# dummyvideo.net
KiCad netlist of a schematic drawn in EAGLE
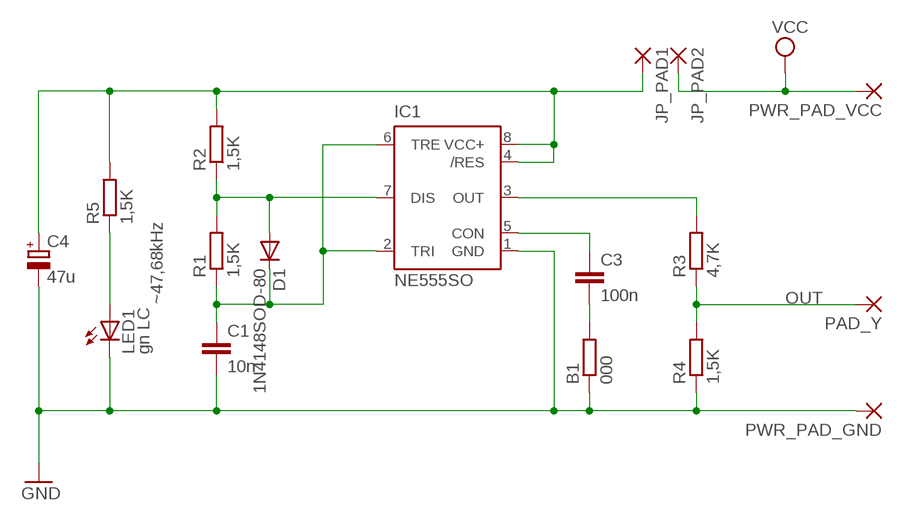
[diagram p0: schematic, sheet 1]

(export (version "E")
  (design (tool "Eeschema 10.0.6"))
  (components
    (comp (ref "B1")
      (value "000")
      (footprint "eagle-import:R1206")
      (libsource (lib "eagle-import") (part "R-EU_R1206"))
    )
    (comp (ref "C1")
      (value "10n")
      (footprint "eagle-import:C0805")
      (libsource (lib "eagle-import") (part "C-EUC0805"))
    )
    (comp (ref "C3")
      (value "100n")
      (footprint "eagle-import:C0805")
      (libsource (lib "eagle-import") (part "C-EUC0805"))
    )
    (comp (ref "C4")
      (value "47u")
      (footprint "eagle-import:153CLV-0505")
      (libsource (lib "eagle-import") (part "CPOL-EU153CLV-0505"))
    )
    (comp (ref "D1")
      (value "1N4148SOD-80")
      (footprint "eagle-import:SOD80C")
      (libsource (lib "eagle-import") (part "1N4148SOD-80"))
    )
    (comp (ref "IC1")
      (value "NE555SO")
      (footprint "eagle-import:SO08")
      (fields (field (name "MPN") "NE555D"))
      (libsource (lib "eagle-import") (part "NE555SO"))
    )
    (comp (ref "JP_PAD1")
      (value "SMD2")
      (footprint "eagle-import:SMD1,27-2,54")
      (libsource (lib "eagle-import") (part "SMD2"))
    )
    (comp (ref "JP_PAD2")
      (value "SMD2")
      (footprint "eagle-import:SMD1,27-2,54")
      (libsource (lib "eagle-import") (part "SMD2"))
    )
    (comp (ref "LED1")
      (value "gn LC")
      (footprint "eagle-import:CHIP-LED0603")
      (libsource (lib "eagle-import") (part "LEDCHIP-LED0603"))
    )
    (comp (ref "PAD_Y")
      (value "SMD2")
      (footprint "eagle-import:SMD1,27-2,54")
      (libsource (lib "eagle-import") (part "SMD2"))
    )
    (comp (ref "PWR_PAD_GND")
      (value "SMD2")
      (footprint "eagle-import:SMD1,27-2,54")
      (libsource (lib "eagle-import") (part "SMD2"))
    )
    (comp (ref "PWR_PAD_VCC")
      (value "SMD2")
      (footprint "eagle-import:SMD1,27-2,54")
      (libsource (lib "eagle-import") (part "SMD2"))
    )
    (comp (ref "R1")
      (value "1,5K")
      (footprint "eagle-import:R0805")
      (libsource (lib "eagle-import") (part "R-EU_R0805"))
    )
    (comp (ref "R2")
      (value "1,5K")
      (footprint "eagle-import:M0805")
      (libsource (lib "eagle-import") (part "R-EU_M0805"))
    )
    (comp (ref "R3")
      (value "4,7K")
      (footprint "eagle-import:R0805")
      (libsource (lib "eagle-import") (part "R-EU_R0805"))
    )
    (comp (ref "R4")
      (value "1,5K")
      (footprint "eagle-import:R0805")
      (libsource (lib "eagle-import") (part "R-EU_R0805"))
    )
    (comp (ref "R5")
      (value "1,5K")
      (footprint "eagle-import:R0805")
      (libsource (lib "eagle-import") (part "R-EU_R0805"))
    )
  )
  (nets
    (net (code "1") (name "/OUT") (class "Default")
      (node (ref "PAD_Y") (pin "1") (pinfunction "P_1") (pintype "passive"))
      (node (ref "R3") (pin "1") (pinfunction "1_1") (pintype "passive"))
      (node (ref "R4") (pin "2") (pinfunction "2_2") (pintype "passive"))
    )
    (net (code "2") (name "GND") (class "Default")
      (node (ref "B1") (pin "1") (pinfunction "1_1") (pintype "passive"))
      (node (ref "B1") (pin "2") (pinfunction "2_2") (pintype "passive"))
      (node (ref "C1") (pin "2") (pinfunction "2_2") (pintype "passive"))
      (node (ref "C3") (pin "2") (pinfunction "2_2") (pintype "passive"))
      (node (ref "C4") (pin "-") (pinfunction "-_-") (pintype "passive"))
      (node (ref "IC1") (pin "1") (pinfunction "GND_1") (pintype "power_in"))
      (node (ref "LED1") (pin "C") (pinfunction "C_C") (pintype "passive"))
      (node (ref "PWR_PAD_GND") (pin "1") (pinfunction "P_1") (pintype "passive"))
      (node (ref "R4") (pin "1") (pinfunction "1_1") (pintype "passive"))
    )
    (net (code "3") (name "Net-(IC1-CON)") (class "Default")
      (node (ref "C3") (pin "1") (pinfunction "1_1") (pintype "passive"))
      (node (ref "IC1") (pin "5") (pinfunction "CON_5") (pintype "input"))
    )
    (net (code "4") (name "Net-(IC1-DIS)") (class "Default")
      (node (ref "D1") (pin "A") (pinfunction "A_A") (pintype "passive"))
      (node (ref "IC1") (pin "7") (pinfunction "DIS_7") (pintype "input"))
      (node (ref "R1") (pin "2") (pinfunction "2_2") (pintype "passive"))
      (node (ref "R2") (pin "1") (pinfunction "1_1") (pintype "passive"))
    )
    (net (code "5") (name "Net-(IC1-OUT)") (class "Default")
      (node (ref "IC1") (pin "3") (pinfunction "OUT_3") (pintype "output"))
      (node (ref "R3") (pin "2") (pinfunction "2_2") (pintype "passive"))
    )
    (net (code "6") (name "Net-(IC1-TRE)") (class "Default")
      (node (ref "C1") (pin "1") (pinfunction "1_1") (pintype "passive"))
      (node (ref "D1") (pin "C") (pinfunction "C_C") (pintype "passive"))
      (node (ref "IC1") (pin "2") (pinfunction "TRI_2") (pintype "input"))
      (node (ref "IC1") (pin "6") (pinfunction "TRE_6") (pintype "input"))
      (node (ref "R1") (pin "1") (pinfunction "1_1") (pintype "passive"))
    )
    (net (code "7") (name "Net-(IC1-VCC+)") (class "Default")
      (node (ref "C4") (pin "+") (pinfunction "+_+") (pintype "passive"))
      (node (ref "IC1") (pin "4") (pinfunction "/RES_4") (pintype "input"))
      (node (ref "IC1") (pin "8") (pinfunction "VCC+_8") (pintype "power_in"))
      (node (ref "JP_PAD1") (pin "1") (pinfunction "P_1") (pintype "passive"))
      (node (ref "R2") (pin "2") (pinfunction "2_2") (pintype "passive"))
      (node (ref "R5") (pin "2") (pinfunction "2_2") (pintype "passive"))
    )
    (net (code "8") (name "Net-(LED1-PadA)") (class "Default")
      (node (ref "LED1") (pin "A") (pinfunction "A_A") (pintype "passive"))
      (node (ref "R5") (pin "1") (pinfunction "1_1") (pintype "passive"))
    )
    (net (code "9") (name "VCC") (class "Default")
      (node (ref "JP_PAD2") (pin "1") (pinfunction "P_1") (pintype "passive"))
      (node (ref "PWR_PAD_VCC") (pin "1") (pinfunction "P_1") (pintype "passive"))
    )
  )
)
